# pcb1_12V.net
KiCad netlist of a schematic drawn in EAGLE
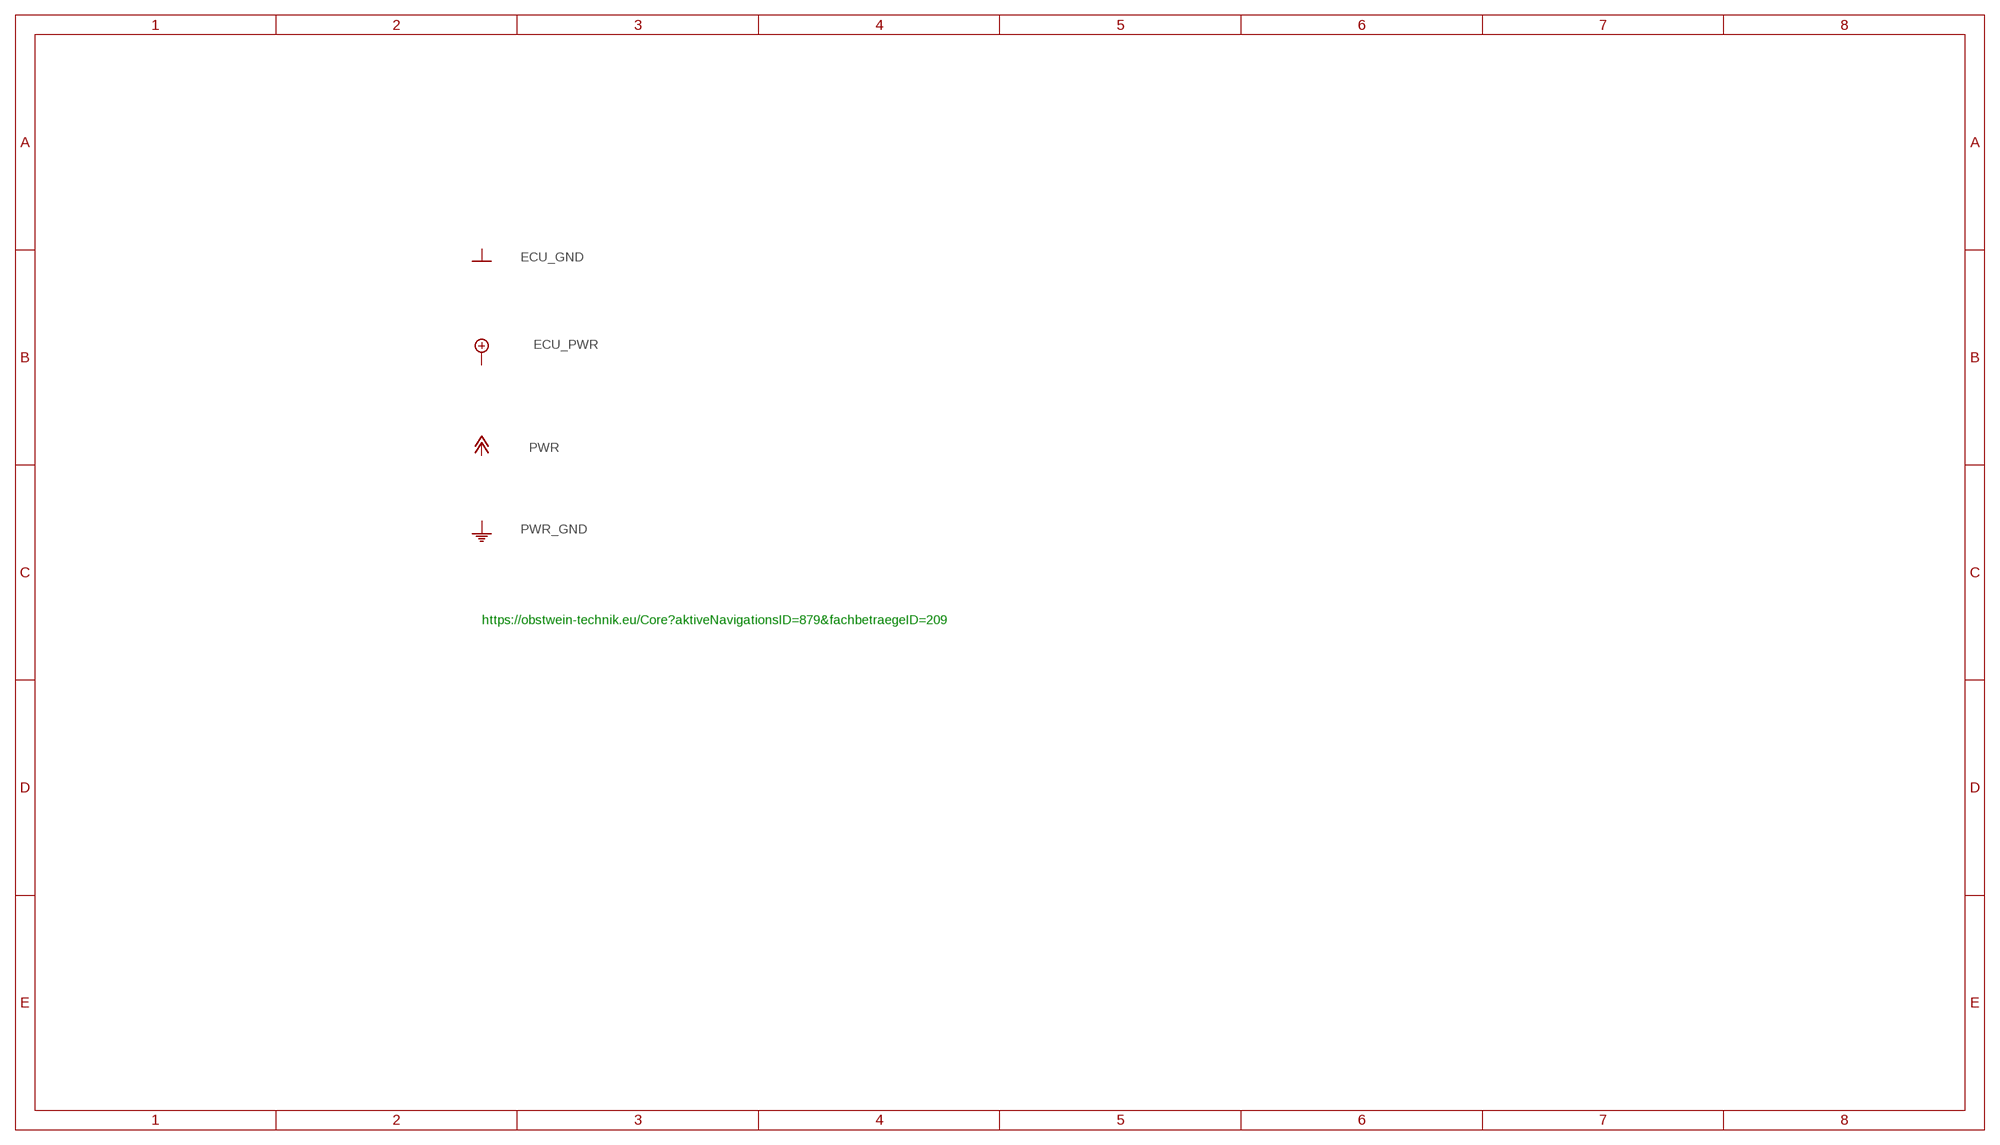
[diagram p0: schematic, sheet 1]
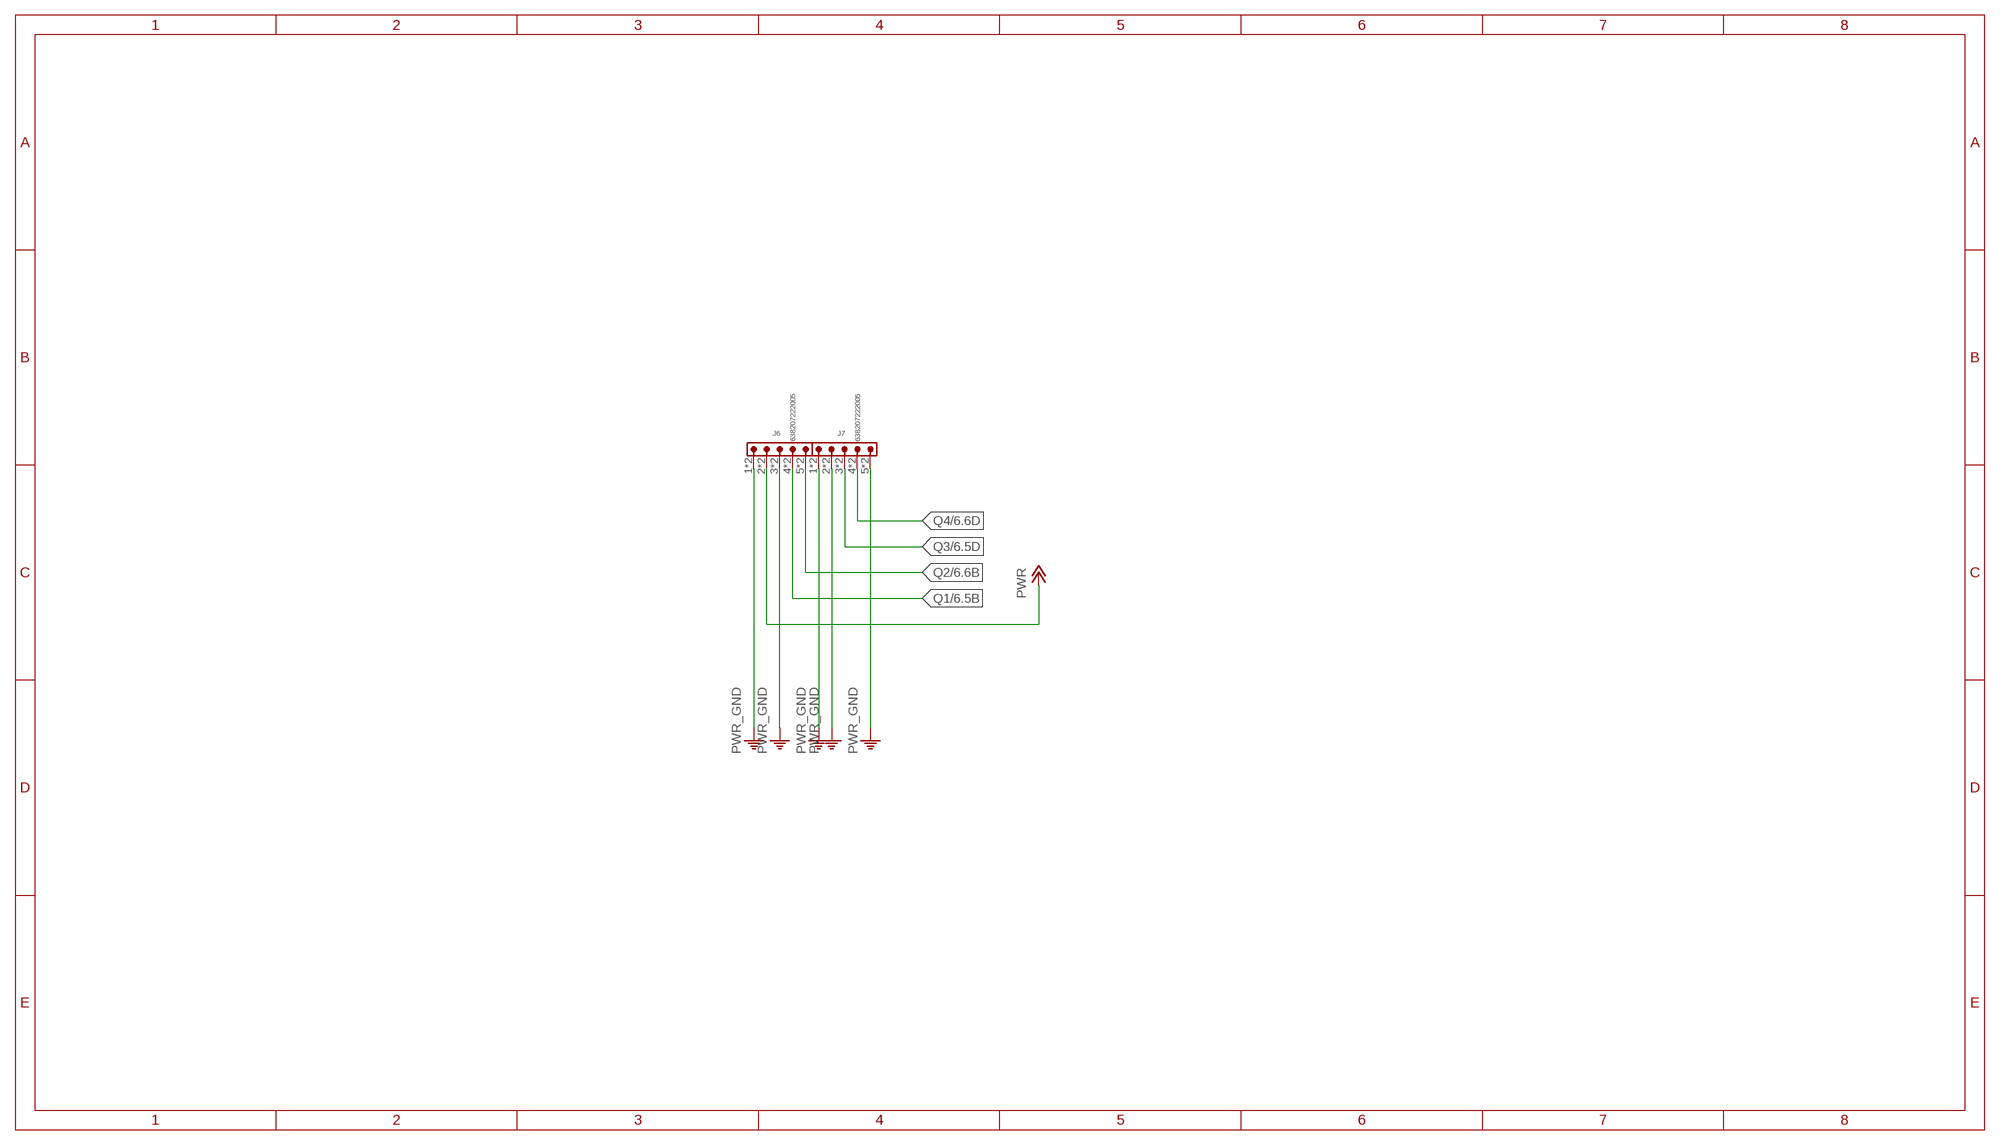
[diagram p1: schematic, sheet 2]
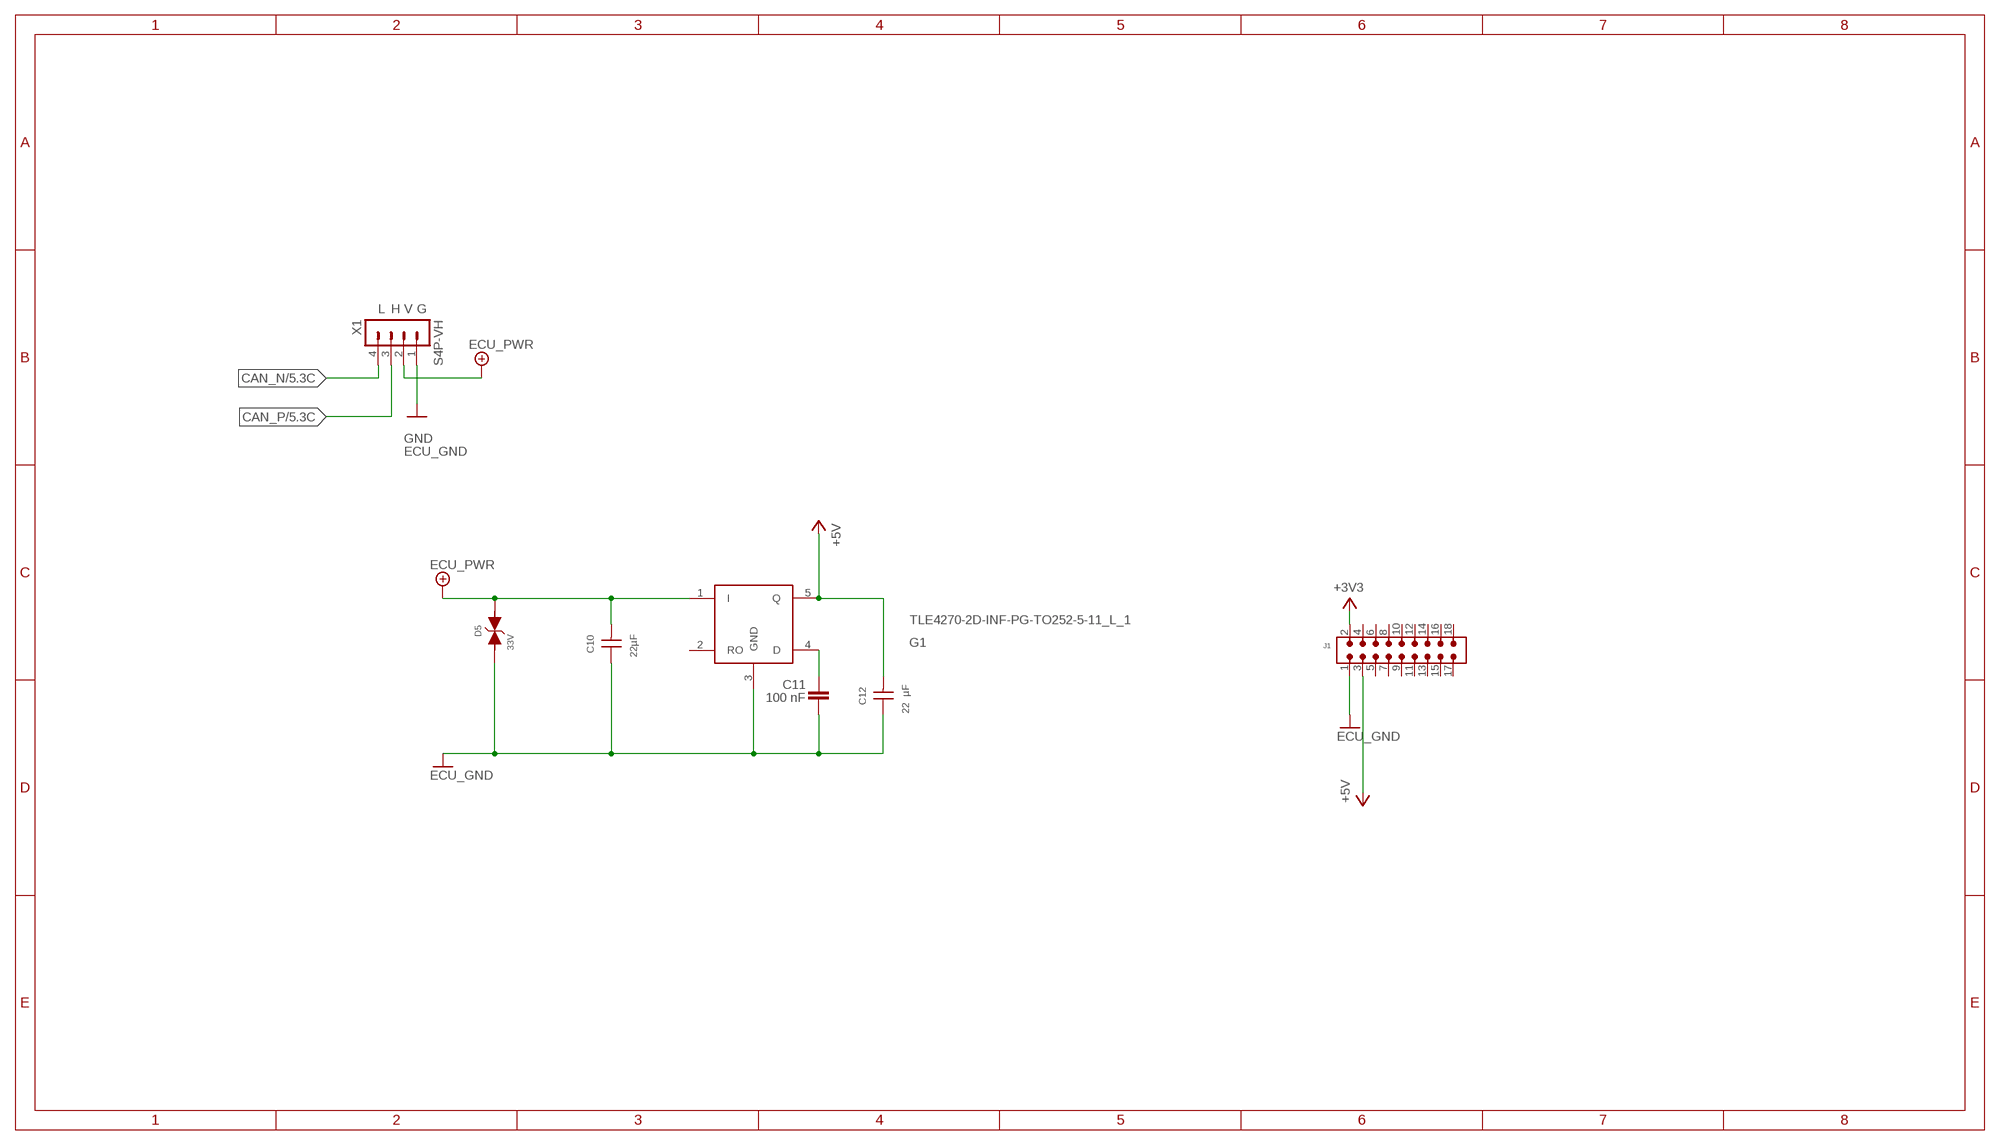
[diagram p2: schematic, sheet 3]
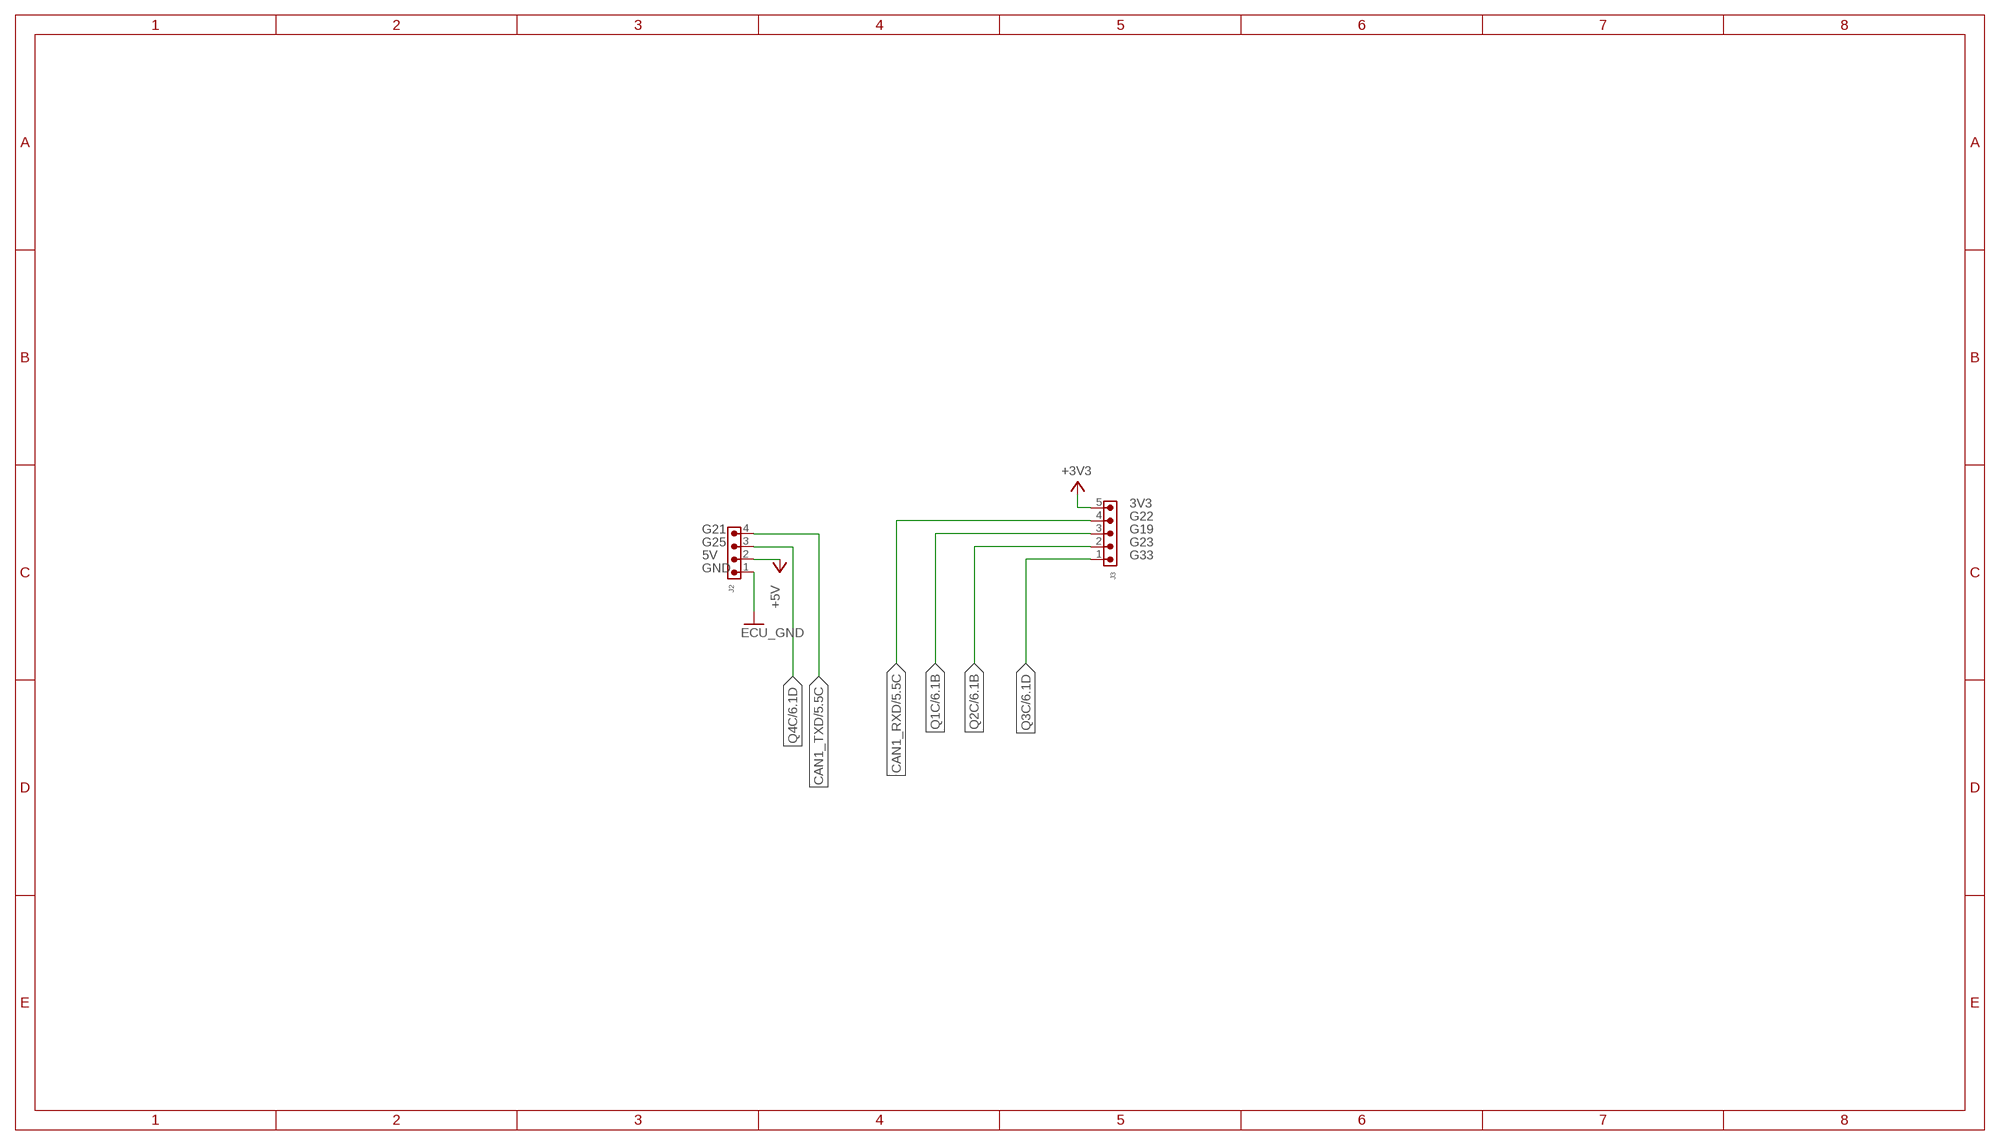
[diagram p3: schematic, sheet 4]
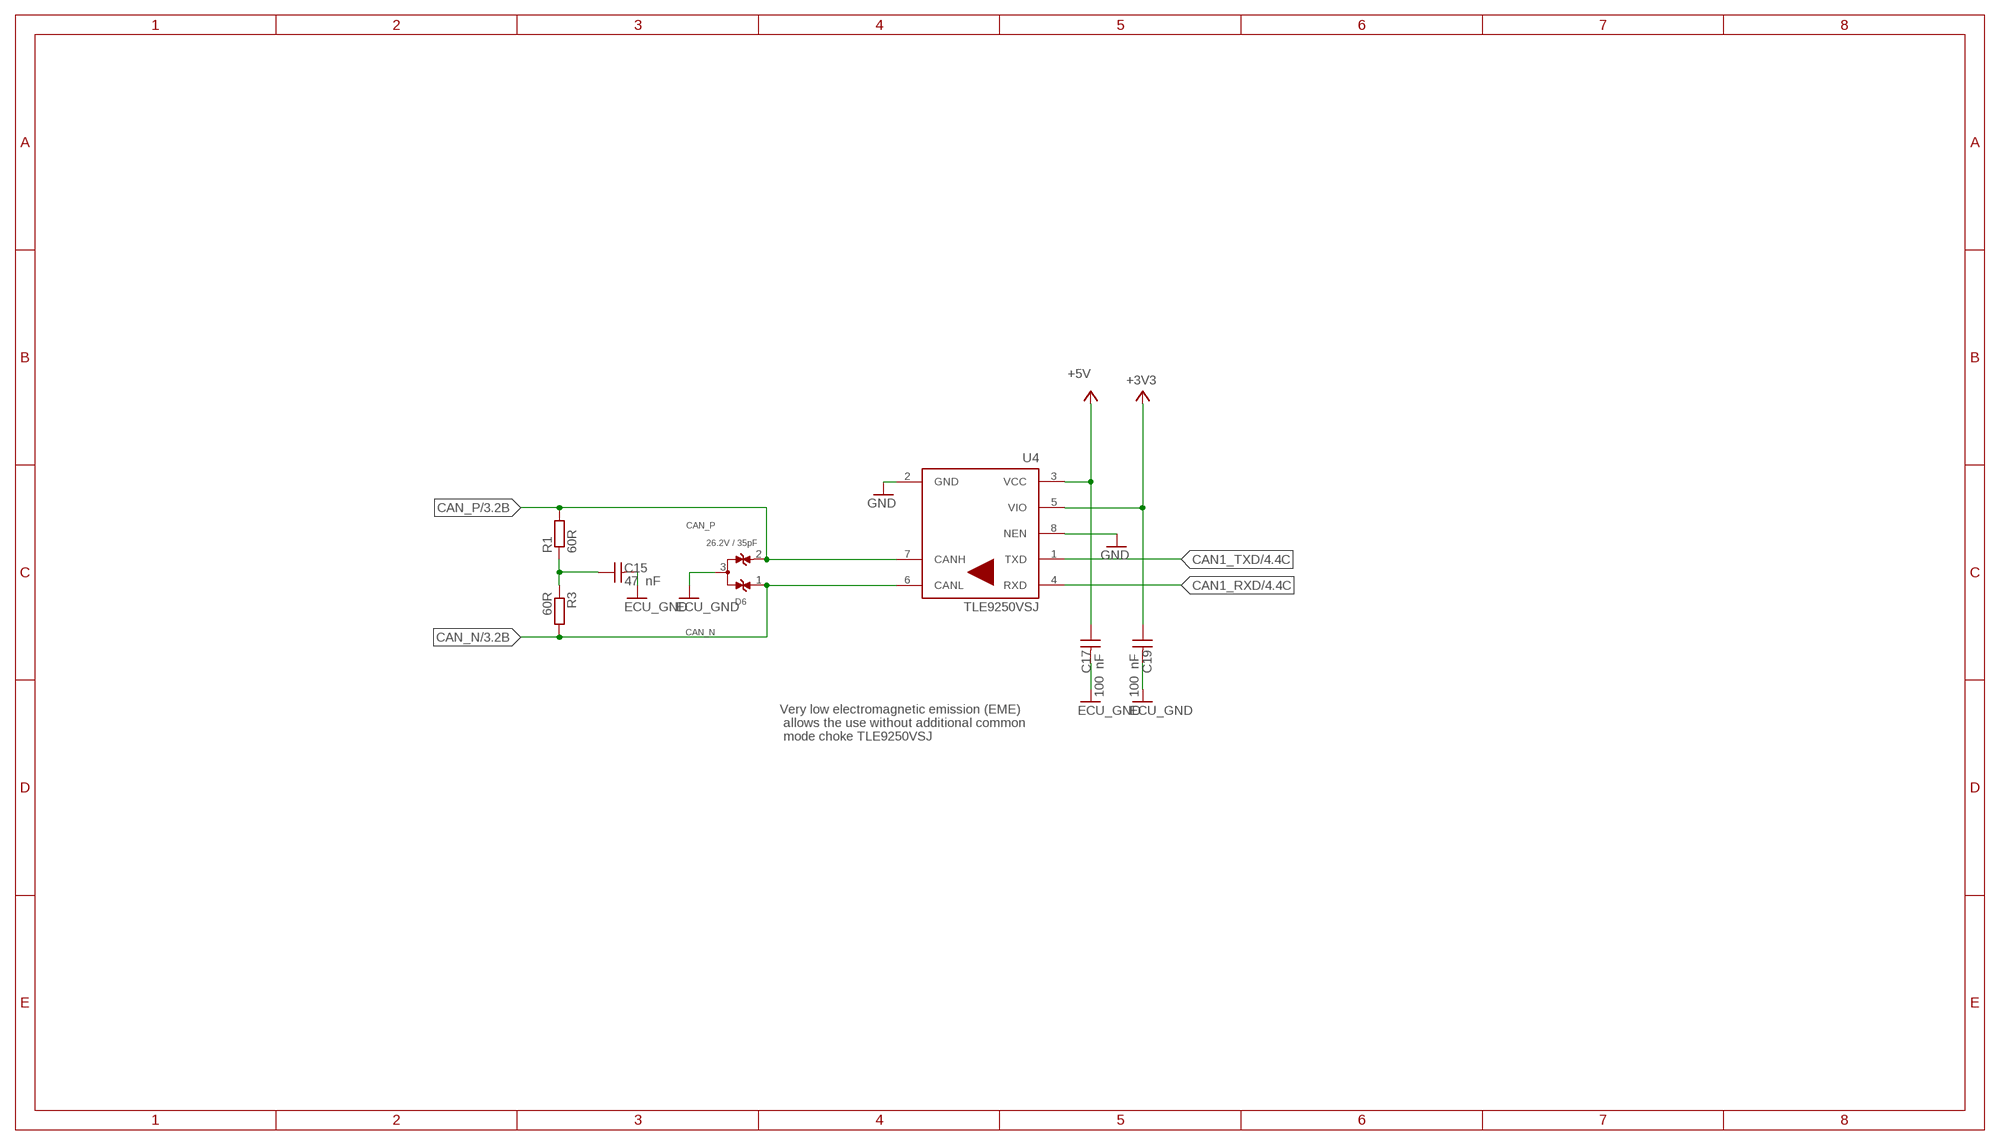
[diagram p4: schematic, sheet 5]
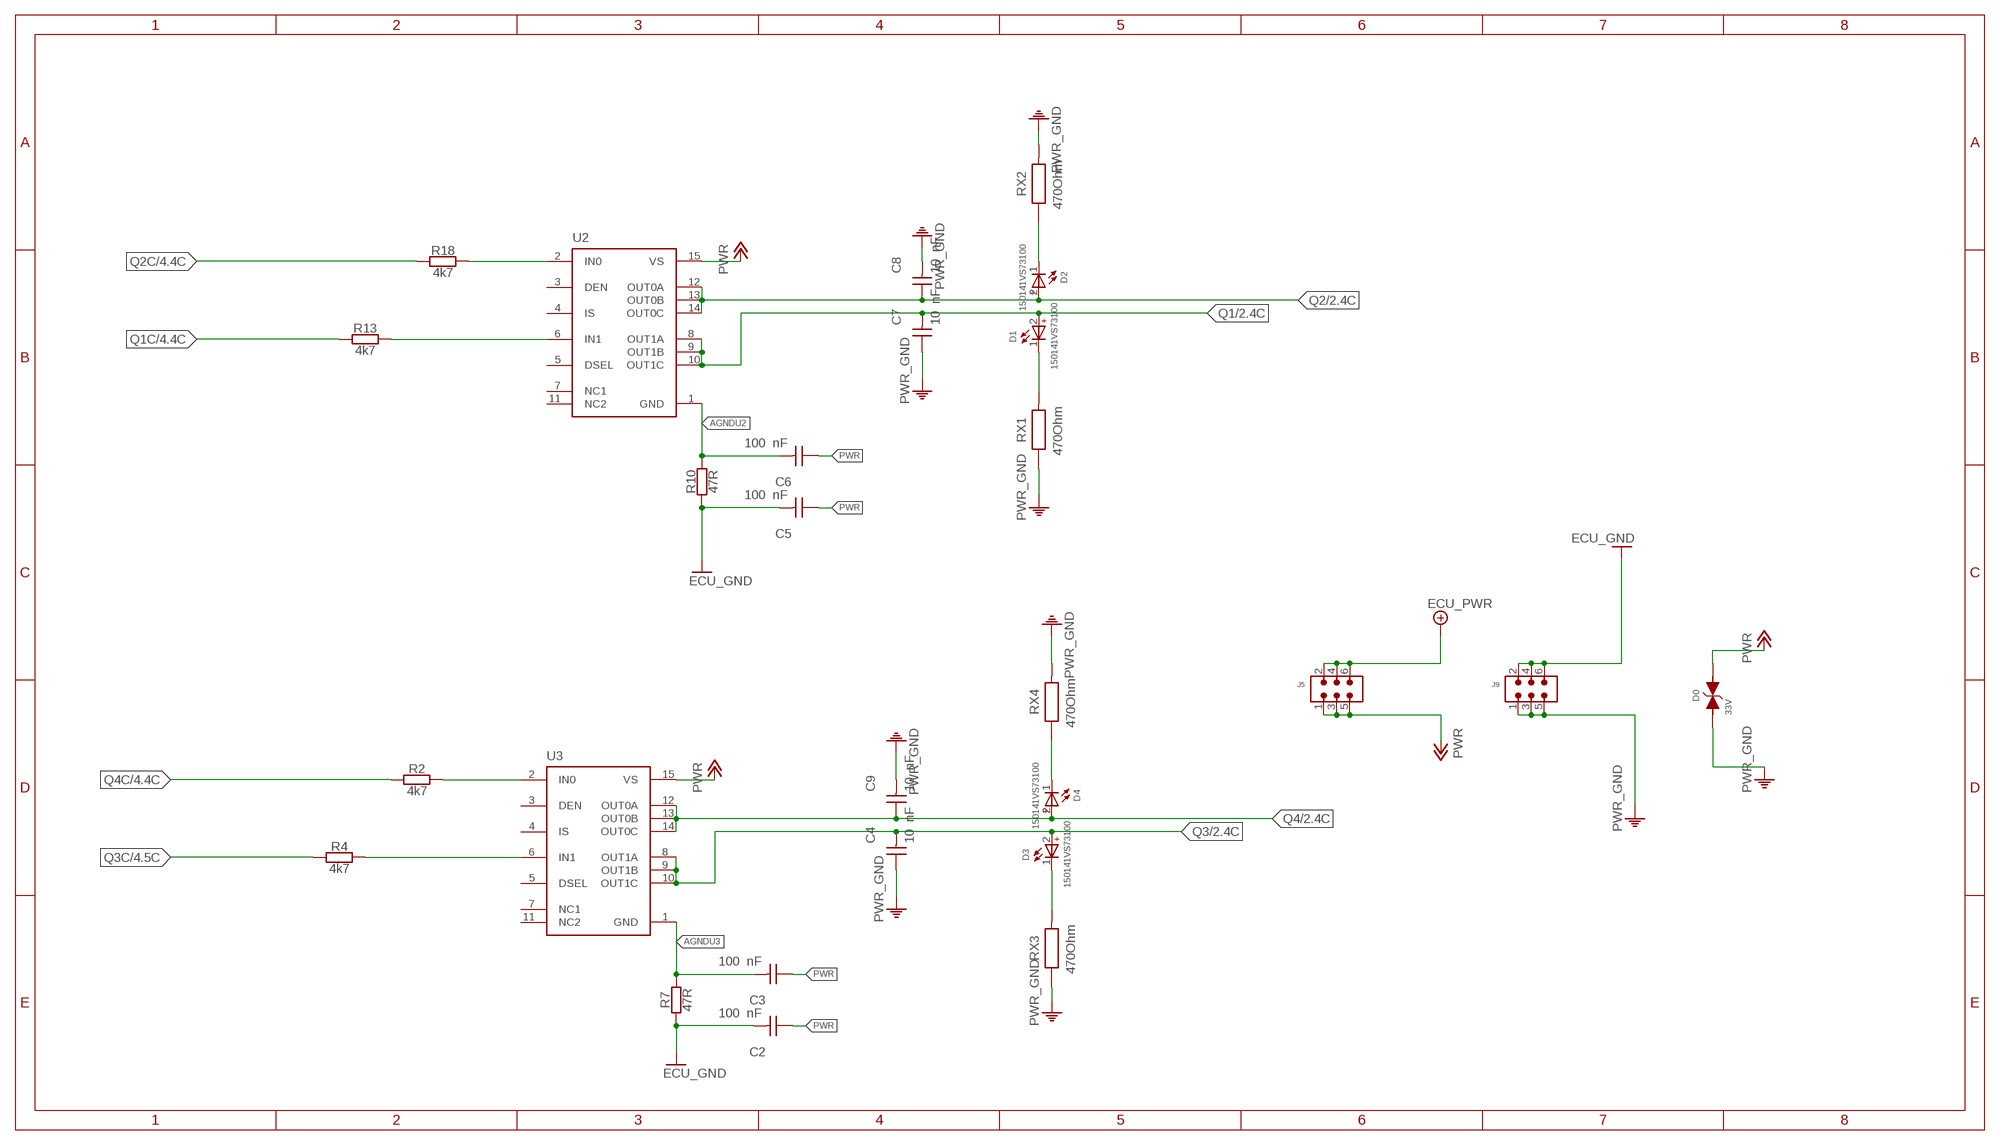
[diagram p5: schematic, sheet 6]

(export (version "E")
  (design (tool "Eeschema 10.0.6"))
  (components
    (comp (ref "C10")
      (value "22µF")
      (footprint "eagle-import:WCAP-CSGP_1210_H2.5")
      (libsource (lib "eagle-import") (part "WCAP-CSGP_1210_H2.5_25V(DC)_885012109014"))
    )
    (comp (ref "C11")
      (value "100 nF")
      (footprint "eagle-import:WCAP-CSGP_0402")
      (libsource (lib "eagle-import") (part "WCAP-CSGP_0402_16V(DC)_885012205037"))
    )
    (comp (ref "C12")
      (value "22 µF")
      (footprint "eagle-import:WCAP-CSGP_0805_H1.25_R")
      (libsource (lib "eagle-import") (part "WCAP-CSGP_0805_H1.25_10V(DC)_885012107011"))
    )
    (comp (ref "D5")
      (value "33V")
      (footprint "eagle-import:WE-TVSP_DO-214AB_BIDIRECTIONAL")
      (libsource (lib "eagle-import") (part "WE-TVSP_DO-214AB_3000W_BI_824551331"))
    )
    (comp (ref "G1")
      (value "TLE4270-2D-INF-PG-TO252-5-11_L_1")
      (footprint "eagle-import:INF-PG-TO252-5-11_L_1PRIMARY")
      (libsource (lib "eagle-import") (part "TLE4270-2D-INF-PG-TO252-5-11_L_1"))
    )
    (comp (ref "J1")
      (value "6130XX21121_61301821121")
      (footprint "eagle-import:61301821121")
      (libsource (lib "eagle-import") (part "6130XX21121_61301821121"))
    )
    (comp (ref "X1")
      (value "S4P-VH")
      (footprint "eagle-import:S4P-VH")
      (libsource (lib "eagle-import") (part "S4P-VH"))
    )
    (comp (ref "C15")
      (value "47 nF")
      (footprint "eagle-import:WCAP-CSGP_0805_H0.8_R")
      (libsource (lib "eagle-import") (part "WCAP-CSGP_0805_H0.8_50V(DC)_R_885012207096"))
    )
    (comp (ref "C17")
      (value "100 nF")
      (footprint "eagle-import:WCAP-CSGP_0805_H0.8_R")
      (libsource (lib "eagle-import") (part "WCAP-CSGP_0805_H0.8_50V(DC)_R_885012207098"))
    )
    (comp (ref "C19")
      (value "100 nF")
      (footprint "eagle-import:WCAP-CSGP_0805_H0.8_R")
      (libsource (lib "eagle-import") (part "WCAP-CSGP_0805_H0.8_50V(DC)_R_885012207098"))
    )
    (comp (ref "D6")
      (value "26.2V / 35pF")
      (footprint "eagle-import:WE-TVS_SOT23-3L")
      (libsource (lib "eagle-import") (part "WE-TVS_SOT23-3L_824098024"))
    )
    (comp (ref "R1")
      (value "60R")
      (footprint "eagle-import:R0805")
      (libsource (lib "eagle-import") (part "R-EU_R0805"))
    )
    (comp (ref "R3")
      (value "60R")
      (footprint "eagle-import:R0805")
      (libsource (lib "eagle-import") (part "R-EU_R0805"))
    )
    (comp (ref "U4")
      (value "TLE9250VSJ")
      (footprint "eagle-import:SOIC127P602X173-8N-V")
      (libsource (lib "eagle-import") (part "TLE9250VSJ"))
    )
    (comp (ref "J2")
      (value "6130XX11121_61300411121")
      (footprint "eagle-import:61300411121")
      (libsource (lib "eagle-import") (part "6130XX11121_61300411121"))
    )
    (comp (ref "J3")
      (value "6130XX11121_61300511121")
      (footprint "eagle-import:61300511121")
      (libsource (lib "eagle-import") (part "6130XX11121_61300511121"))
    )
    (comp (ref "C2")
      (value "100 nF")
      (footprint "eagle-import:WCAP-CSGP_0805_H0.8_R")
      (libsource (lib "eagle-import") (part "WCAP-CSGP_0805_H0.8_50V(DC)_R_885012207098"))
    )
    (comp (ref "C3")
      (value "100 nF")
      (footprint "eagle-import:WCAP-CSGP_0805_H0.8_R")
      (libsource (lib "eagle-import") (part "WCAP-CSGP_0805_H0.8_50V(DC)_R_885012207098"))
    )
    (comp (ref "C4")
      (value "10 nF")
      (footprint "eagle-import:WCAP-CSGP_0805_H0.8_R")
      (libsource (lib "eagle-import") (part "WCAP-CSGP_0805_H0.8_50V(DC)_R_885012207092"))
    )
    (comp (ref "C5")
      (value "100 nF")
      (footprint "eagle-import:WCAP-CSGP_0805_H0.8_R")
      (libsource (lib "eagle-import") (part "WCAP-CSGP_0805_H0.8_50V(DC)_R_885012207098"))
    )
    (comp (ref "C6")
      (value "100 nF")
      (footprint "eagle-import:WCAP-CSGP_0805_H0.8_R")
      (libsource (lib "eagle-import") (part "WCAP-CSGP_0805_H0.8_50V(DC)_R_885012207098"))
    )
    (comp (ref "C7")
      (value "10 nF")
      (footprint "eagle-import:WCAP-CSGP_0805_H0.8_R")
      (libsource (lib "eagle-import") (part "WCAP-CSGP_0805_H0.8_50V(DC)_R_885012207092"))
    )
    (comp (ref "C8")
      (value "10 nF")
      (footprint "eagle-import:WCAP-CSGP_0805_H0.8_R")
      (libsource (lib "eagle-import") (part "WCAP-CSGP_0805_H0.8_50V(DC)_R_885012207092"))
    )
    (comp (ref "C9")
      (value "10 nF")
      (footprint "eagle-import:WCAP-CSGP_0805_H0.8_R")
      (libsource (lib "eagle-import") (part "WCAP-CSGP_0805_H0.8_50V(DC)_R_885012207092"))
    )
    (comp (ref "D0")
      (value "33V")
      (footprint "eagle-import:WE-TVSP_DO-214AB_BIDIRECTIONAL")
      (libsource (lib "eagle-import") (part "WE-TVSP_DO-214AB_3000W_BI_824551331"))
    )
    (comp (ref "D1")
      (value "150141VS73100")
      (footprint "eagle-import:WL-SMTW_3528")
      (libsource (lib "eagle-import") (part "WL-SMTW_3528_150141VS73100"))
    )
    (comp (ref "D2")
      (value "150141VS73100")
      (footprint "eagle-import:WL-SMTW_3528")
      (libsource (lib "eagle-import") (part "WL-SMTW_3528_150141VS73100"))
    )
    (comp (ref "D3")
      (value "150141VS73100")
      (footprint "eagle-import:WL-SMTW_3528")
      (libsource (lib "eagle-import") (part "WL-SMTW_3528_150141VS73100"))
    )
    (comp (ref "D4")
      (value "150141VS73100")
      (footprint "eagle-import:WL-SMTW_3528")
      (libsource (lib "eagle-import") (part "WL-SMTW_3528_150141VS73100"))
    )
    (comp (ref "J5")
      (value "6130XX21121_61300621121")
      (footprint "eagle-import:61300621121")
      (libsource (lib "eagle-import") (part "6130XX21121_61300621121"))
    )
    (comp (ref "J9")
      (value "6130XX21121_61300621121")
      (footprint "eagle-import:61300621121")
      (libsource (lib "eagle-import") (part "6130XX21121_61300621121"))
    )
    (comp (ref "R2")
      (value "4k7")
      (footprint "eagle-import:R0805")
      (libsource (lib "eagle-import") (part "R-EU_R0805"))
    )
    (comp (ref "R4")
      (value "4k7")
      (footprint "eagle-import:R0805")
      (libsource (lib "eagle-import") (part "R-EU_R0805"))
    )
    (comp (ref "R7")
      (value "47R")
      (footprint "eagle-import:R0805")
      (libsource (lib "eagle-import") (part "R-EU_R0805"))
    )
    (comp (ref "R10")
      (value "47R")
      (footprint "eagle-import:R0805")
      (libsource (lib "eagle-import") (part "R-EU_R0805"))
    )
    (comp (ref "R13")
      (value "4k7")
      (footprint "eagle-import:R0805")
      (libsource (lib "eagle-import") (part "R-EU_R0805"))
    )
    (comp (ref "R18")
      (value "4k7")
      (footprint "eagle-import:R0805")
      (libsource (lib "eagle-import") (part "R-EU_R0805"))
    )
    (comp (ref "RX1")
      (value "470Ohm")
      (footprint "eagle-import:WRIS-KWKB_0612")
      (libsource (lib "eagle-import") (part "WRIS-KWKB_0612_561020132023"))
    )
    (comp (ref "RX2")
      (value "470Ohm")
      (footprint "eagle-import:WRIS-KWKB_0612")
      (libsource (lib "eagle-import") (part "WRIS-KWKB_0612_561020132023"))
    )
    (comp (ref "RX3")
      (value "470Ohm")
      (footprint "eagle-import:WRIS-KWKB_0612")
      (libsource (lib "eagle-import") (part "WRIS-KWKB_0612_561020132023"))
    )
    (comp (ref "RX4")
      (value "470Ohm")
      (footprint "eagle-import:WRIS-KWKB_0612")
      (libsource (lib "eagle-import") (part "WRIS-KWKB_0612_561020132023"))
    )
    (comp (ref "U2")
      (value "BTS7030-2EPA")
      (footprint "eagle-import:SOP65P600X115-15N-V")
      (libsource (lib "eagle-import") (part "BTS7030-2EPA"))
    )
    (comp (ref "U3")
      (value "BTS7030-2EPA")
      (footprint "eagle-import:SOP65P600X115-15N-V")
      (libsource (lib "eagle-import") (part "BTS7030-2EPA"))
    )
    (comp (ref "J6")
      (value "638207222005")
      (footprint "eagle-import:638207222005")
      (libsource (lib "eagle-import") (part "638207222005"))
    )
    (comp (ref "J7")
      (value "638207222005")
      (footprint "eagle-import:638207222005")
      (libsource (lib "eagle-import") (part "638207222005"))
    )
  )
  (nets
    (net (code "1") (name "+3V3") (class "Default")
      (node (ref "C19") (pin "1") (pinfunction "1_1") (pintype "passive"))
      (node (ref "J1") (pin "2") (pinfunction "2_2") (pintype "passive"))
      (node (ref "J3") (pin "5") (pinfunction "5_5") (pintype "passive"))
      (node (ref "U4") (pin "5") (pinfunction "VIO_5") (pintype "input"))
    )
    (net (code "2") (name "+5V") (class "Default")
      (node (ref "C12") (pin "2") (pinfunction "2_2") (pintype "passive"))
      (node (ref "C17") (pin "1") (pinfunction "1_1") (pintype "passive"))
      (node (ref "G1") (pin "5") (pinfunction "Q_5") (pintype "power_in"))
      (node (ref "J1") (pin "3") (pinfunction "3_3") (pintype "passive"))
      (node (ref "J2") (pin "2") (pinfunction "2_2") (pintype "passive"))
      (node (ref "U4") (pin "3") (pinfunction "VCC_3") (pintype "input"))
    )
    (net (code "3") (name "AGNDU2") (class "Default")
      (node (ref "C6") (pin "2") (pinfunction "2_2") (pintype "passive"))
      (node (ref "R10") (pin "2") (pinfunction "2_2") (pintype "passive"))
      (node (ref "U2") (pin "1") (pinfunction "GND_1") (pintype "power_in"))
    )
    (net (code "4") (name "AGNDU3") (class "Default")
      (node (ref "C3") (pin "2") (pinfunction "2_2") (pintype "passive"))
      (node (ref "R7") (pin "2") (pinfunction "2_2") (pintype "passive"))
      (node (ref "U3") (pin "1") (pinfunction "GND_1") (pintype "power_in"))
    )
    (net (code "5") (name "CAN1_RXD") (class "Default")
      (node (ref "J3") (pin "4") (pinfunction "4_4") (pintype "passive"))
      (node (ref "U4") (pin "4") (pinfunction "RXD_4") (pintype "output"))
    )
    (net (code "6") (name "CAN1_TXD") (class "Default")
      (node (ref "J2") (pin "4") (pinfunction "4_4") (pintype "passive"))
      (node (ref "U4") (pin "1") (pinfunction "TXD_1") (pintype "input"))
    )
    (net (code "7") (name "CAN_N") (class "Default")
      (node (ref "D6") (pin "1") (pinfunction "1_1") (pintype "passive"))
      (node (ref "R3") (pin "2") (pinfunction "2_2") (pintype "passive"))
      (node (ref "U4") (pin "6") (pinfunction "CANL_6") (pintype "bidirectional"))
      (node (ref "X1") (pin "4") (pinfunction "4_4") (pintype "passive"))
    )
    (net (code "8") (name "CAN_P") (class "Default")
      (node (ref "D6") (pin "2") (pinfunction "2_2") (pintype "passive"))
      (node (ref "R1") (pin "2") (pinfunction "2_2") (pintype "passive"))
      (node (ref "U4") (pin "7") (pinfunction "CANH_7") (pintype "bidirectional"))
      (node (ref "X1") (pin "3") (pinfunction "3_3") (pintype "passive"))
    )
    (net (code "9") (name "ECU_GND") (class "Default")
      (node (ref "C10") (pin "1") (pinfunction "1_1") (pintype "passive"))
      (node (ref "C11") (pin "2") (pinfunction "2_2") (pintype "passive"))
      (node (ref "C12") (pin "1") (pinfunction "1_1") (pintype "passive"))
      (node (ref "C15") (pin "2") (pinfunction "2_2") (pintype "passive"))
      (node (ref "C17") (pin "2") (pinfunction "2_2") (pintype "passive"))
      (node (ref "C19") (pin "2") (pinfunction "2_2") (pintype "passive"))
      (node (ref "C2") (pin "2") (pinfunction "2_2") (pintype "passive"))
      (node (ref "C5") (pin "2") (pinfunction "2_2") (pintype "passive"))
      (node (ref "D5") (pin "1") (pinfunction "1_1") (pintype "passive"))
      (node (ref "D6") (pin "3") (pinfunction "3_3") (pintype "passive"))
      (node (ref "G1") (pin "3") (pinfunction "GND_3") (pintype "power_in"))
      (node (ref "J1") (pin "1") (pinfunction "1_1") (pintype "passive"))
      (node (ref "J2") (pin "1") (pinfunction "1_1") (pintype "passive"))
      (node (ref "J9") (pin "2") (pinfunction "2_2") (pintype "passive"))
      (node (ref "J9") (pin "4") (pinfunction "4_4") (pintype "passive"))
      (node (ref "J9") (pin "6") (pinfunction "6_6") (pintype "passive"))
      (node (ref "R10") (pin "1") (pinfunction "1_1") (pintype "passive"))
      (node (ref "R7") (pin "1") (pinfunction "1_1") (pintype "passive"))
      (node (ref "U4") (pin "2") (pinfunction "GND_2") (pintype "power_in"))
      (node (ref "U4") (pin "8") (pinfunction "NEN_8") (pintype "input"))
      (node (ref "X1") (pin "1") (pinfunction "1_1") (pintype "passive"))
    )
    (net (code "10") (name "ECU_PWR") (class "Default")
      (node (ref "C10") (pin "2") (pinfunction "2_2") (pintype "passive"))
      (node (ref "D5") (pin "2") (pinfunction "2_2") (pintype "passive"))
      (node (ref "G1") (pin "1") (pinfunction "I_1") (pintype "power_in"))
      (node (ref "J5") (pin "2") (pinfunction "2_2") (pintype "passive"))
      (node (ref "J5") (pin "4") (pinfunction "4_4") (pintype "passive"))
      (node (ref "J5") (pin "6") (pinfunction "6_6") (pintype "passive"))
      (node (ref "X1") (pin "2") (pinfunction "2_2") (pintype "passive"))
    )
    (net (code "11") (name "Net-(C15-Pad1)") (class "Default")
      (node (ref "C15") (pin "1") (pinfunction "1_1") (pintype "passive"))
      (node (ref "R1") (pin "1") (pinfunction "1_1") (pintype "passive"))
      (node (ref "R3") (pin "1") (pinfunction "1_1") (pintype "passive"))
    )
    (net (code "12") (name "Net-(D1--)") (class "Default")
      (node (ref "D1") (pin "1") (pinfunction "-_1") (pintype "passive"))
      (node (ref "RX1") (pin "2") (pinfunction "2_2") (pintype "passive"))
    )
    (net (code "13") (name "Net-(D2--)") (class "Default")
      (node (ref "D2") (pin "1") (pinfunction "-_1") (pintype "passive"))
      (node (ref "RX2") (pin "1") (pinfunction "1_1") (pintype "passive"))
    )
    (net (code "14") (name "Net-(D3--)") (class "Default")
      (node (ref "D3") (pin "1") (pinfunction "-_1") (pintype "passive"))
      (node (ref "RX3") (pin "2") (pinfunction "2_2") (pintype "passive"))
    )
    (net (code "15") (name "Net-(D4--)") (class "Default")
      (node (ref "D4") (pin "1") (pinfunction "-_1") (pintype "passive"))
      (node (ref "RX4") (pin "1") (pinfunction "1_1") (pintype "passive"))
    )
    (net (code "16") (name "Net-(G1-D)") (class "Default")
      (node (ref "C11") (pin "1") (pinfunction "1_1") (pintype "passive"))
      (node (ref "G1") (pin "4") (pinfunction "D_4") (pintype "bidirectional"))
    )
    (net (code "17") (name "Net-(U2-IN0)") (class "Default")
      (node (ref "R18") (pin "2") (pinfunction "2_2") (pintype "passive"))
      (node (ref "U2") (pin "2") (pinfunction "IN0_2") (pintype "input"))
    )
    (net (code "18") (name "Net-(U2-IN1)") (class "Default")
      (node (ref "R13") (pin "2") (pinfunction "2_2") (pintype "passive"))
      (node (ref "U2") (pin "6") (pinfunction "IN1_6") (pintype "input"))
    )
    (net (code "19") (name "Net-(U3-IN0)") (class "Default")
      (node (ref "R2") (pin "2") (pinfunction "2_2") (pintype "passive"))
      (node (ref "U3") (pin "2") (pinfunction "IN0_2") (pintype "input"))
    )
    (net (code "20") (name "Net-(U3-IN1)") (class "Default")
      (node (ref "R4") (pin "2") (pinfunction "2_2") (pintype "passive"))
      (node (ref "U3") (pin "6") (pinfunction "IN1_6") (pintype "input"))
    )
    (net (code "21") (name "PWR") (class "Default")
      (node (ref "C2") (pin "1") (pinfunction "1_1") (pintype "passive"))
      (node (ref "C3") (pin "1") (pinfunction "1_1") (pintype "passive"))
      (node (ref "C5") (pin "1") (pinfunction "1_1") (pintype "passive"))
      (node (ref "C6") (pin "1") (pinfunction "1_1") (pintype "passive"))
      (node (ref "D0") (pin "2") (pinfunction "2_2") (pintype "passive"))
      (node (ref "J5") (pin "1") (pinfunction "1_1") (pintype "passive"))
      (node (ref "J5") (pin "3") (pinfunction "3_3") (pintype "passive"))
      (node (ref "J5") (pin "5") (pinfunction "5_5") (pintype "passive"))
      (node (ref "J6") (pin "2") (pinfunction "2_2") (pintype "passive"))
      (node (ref "J6") (pin "A2") (pinfunction "2_A2") (pintype "passive"))
      (node (ref "U2") (pin "15") (pinfunction "VS_15") (pintype "power_in"))
      (node (ref "U3") (pin "15") (pinfunction "VS_15") (pintype "power_in"))
    )
    (net (code "22") (name "PWR_GND") (class "Default")
      (node (ref "C4") (pin "1") (pinfunction "1_1") (pintype "passive"))
      (node (ref "C7") (pin "1") (pinfunction "1_1") (pintype "passive"))
      (node (ref "C8") (pin "2") (pinfunction "2_2") (pintype "passive"))
      (node (ref "C9") (pin "2") (pinfunction "2_2") (pintype "passive"))
      (node (ref "D0") (pin "1") (pinfunction "1_1") (pintype "passive"))
      (node (ref "J6") (pin "1") (pinfunction "1_1") (pintype "passive"))
      (node (ref "J6") (pin "3") (pinfunction "3_3") (pintype "passive"))
      (node (ref "J6") (pin "A1") (pinfunction "1_A1") (pintype "passive"))
      (node (ref "J6") (pin "A3") (pinfunction "3_A3") (pintype "passive"))
      (node (ref "J7") (pin "1") (pinfunction "1_1") (pintype "passive"))
      (node (ref "J7") (pin "2") (pinfunction "2_2") (pintype "passive"))
      (node (ref "J7") (pin "5") (pinfunction "5_5") (pintype "passive"))
      (node (ref "J7") (pin "A1") (pinfunction "1_A1") (pintype "passive"))
      (node (ref "J7") (pin "A2") (pinfunction "2_A2") (pintype "passive"))
      (node (ref "J7") (pin "A5") (pinfunction "5_A5") (pintype "passive"))
      (node (ref "J9") (pin "1") (pinfunction "1_1") (pintype "passive"))
      (node (ref "J9") (pin "3") (pinfunction "3_3") (pintype "passive"))
      (node (ref "J9") (pin "5") (pinfunction "5_5") (pintype "passive"))
      (node (ref "RX1") (pin "1") (pinfunction "1_1") (pintype "passive"))
      (node (ref "RX2") (pin "2") (pinfunction "2_2") (pintype "passive"))
      (node (ref "RX3") (pin "1") (pinfunction "1_1") (pintype "passive"))
      (node (ref "RX4") (pin "2") (pinfunction "2_2") (pintype "passive"))
    )
    (net (code "23") (name "Q1") (class "Default")
      (node (ref "C7") (pin "2") (pinfunction "2_2") (pintype "passive"))
      (node (ref "D1") (pin "2") (pinfunction "+_2") (pintype "passive"))
      (node (ref "J6") (pin "4") (pinfunction "4_4") (pintype "passive"))
      (node (ref "J6") (pin "A4") (pinfunction "4_A4") (pintype "passive"))
      (node (ref "U2") (pin "10") (pinfunction "OUT1C_10") (pintype "output"))
      (node (ref "U2") (pin "8") (pinfunction "OUT1A_8") (pintype "output"))
      (node (ref "U2") (pin "9") (pinfunction "OUT1B_9") (pintype "output"))
    )
    (net (code "24") (name "Q1C") (class "Default")
      (node (ref "J3") (pin "3") (pinfunction "3_3") (pintype "passive"))
      (node (ref "R13") (pin "1") (pinfunction "1_1") (pintype "passive"))
    )
    (net (code "25") (name "Q2") (class "Default")
      (node (ref "C8") (pin "1") (pinfunction "1_1") (pintype "passive"))
      (node (ref "D2") (pin "2") (pinfunction "+_2") (pintype "passive"))
      (node (ref "J6") (pin "5") (pinfunction "5_5") (pintype "passive"))
      (node (ref "J6") (pin "A5") (pinfunction "5_A5") (pintype "passive"))
      (node (ref "U2") (pin "12") (pinfunction "OUT0A_12") (pintype "output"))
      (node (ref "U2") (pin "13") (pinfunction "OUT0B_13") (pintype "output"))
      (node (ref "U2") (pin "14") (pinfunction "OUT0C_14") (pintype "output"))
    )
    (net (code "26") (name "Q2C") (class "Default")
      (node (ref "J3") (pin "2") (pinfunction "2_2") (pintype "passive"))
      (node (ref "R18") (pin "1") (pinfunction "1_1") (pintype "passive"))
    )
    (net (code "27") (name "Q3") (class "Default")
      (node (ref "C4") (pin "2") (pinfunction "2_2") (pintype "passive"))
      (node (ref "D3") (pin "2") (pinfunction "+_2") (pintype "passive"))
      (node (ref "J7") (pin "3") (pinfunction "3_3") (pintype "passive"))
      (node (ref "J7") (pin "A3") (pinfunction "3_A3") (pintype "passive"))
      (node (ref "U3") (pin "10") (pinfunction "OUT1C_10") (pintype "output"))
      (node (ref "U3") (pin "8") (pinfunction "OUT1A_8") (pintype "output"))
      (node (ref "U3") (pin "9") (pinfunction "OUT1B_9") (pintype "output"))
    )
    (net (code "28") (name "Q3C") (class "Default")
      (node (ref "J3") (pin "1") (pinfunction "1_1") (pintype "passive"))
      (node (ref "R4") (pin "1") (pinfunction "1_1") (pintype "passive"))
    )
    (net (code "29") (name "Q4") (class "Default")
      (node (ref "C9") (pin "1") (pinfunction "1_1") (pintype "passive"))
      (node (ref "D4") (pin "2") (pinfunction "+_2") (pintype "passive"))
      (node (ref "J7") (pin "4") (pinfunction "4_4") (pintype "passive"))
      (node (ref "J7") (pin "A4") (pinfunction "4_A4") (pintype "passive"))
      (node (ref "U3") (pin "12") (pinfunction "OUT0A_12") (pintype "output"))
      (node (ref "U3") (pin "13") (pinfunction "OUT0B_13") (pintype "output"))
      (node (ref "U3") (pin "14") (pinfunction "OUT0C_14") (pintype "output"))
    )
    (net (code "30") (name "Q4C") (class "Default")
      (node (ref "J2") (pin "3") (pinfunction "3_3") (pintype "passive"))
      (node (ref "R2") (pin "1") (pinfunction "1_1") (pintype "passive"))
    )
    (net (code "31") (name "unconnected-(G1-RO-Pad2)") (class "Default")
      (node (ref "G1") (pin "2") (pinfunction "RO_2") (pintype "output"))
    )
    (net (code "32") (name "unconnected-(J1-Pad4)") (class "Default")
      (node (ref "J1") (pin "4") (pinfunction "4_4") (pintype "passive"))
    )
    (net (code "33") (name "unconnected-(J1-Pad5)") (class "Default")
      (node (ref "J1") (pin "5") (pinfunction "5_5") (pintype "passive"))
    )
    (net (code "34") (name "unconnected-(J1-Pad6)") (class "Default")
      (node (ref "J1") (pin "6") (pinfunction "6_6") (pintype "passive"))
    )
    (net (code "35") (name "unconnected-(J1-Pad7)") (class "Default")
      (node (ref "J1") (pin "7") (pinfunction "7_7") (pintype "passive"))
    )
    (net (code "36") (name "unconnected-(J1-Pad8)") (class "Default")
      (node (ref "J1") (pin "8") (pinfunction "8_8") (pintype "passive"))
    )
    (net (code "37") (name "unconnected-(J1-Pad9)") (class "Default")
      (node (ref "J1") (pin "9") (pinfunction "9_9") (pintype "passive"))
    )
    (net (code "38") (name "unconnected-(J1-Pad10)") (class "Default")
      (node (ref "J1") (pin "10") (pinfunction "10_10") (pintype "passive"))
    )
    (net (code "39") (name "unconnected-(J1-Pad11)") (class "Default")
      (node (ref "J1") (pin "11") (pinfunction "11_11") (pintype "passive"))
    )
    (net (code "40") (name "unconnected-(J1-Pad12)") (class "Default")
      (node (ref "J1") (pin "12") (pinfunction "12_12") (pintype "passive"))
    )
    (net (code "41") (name "unconnected-(J1-Pad13)") (class "Default")
      (node (ref "J1") (pin "13") (pinfunction "13_13") (pintype "passive"))
    )
    (net (code "42") (name "unconnected-(J1-Pad14)") (class "Default")
      (node (ref "J1") (pin "14") (pinfunction "14_14") (pintype "passive"))
    )
    (net (code "43") (name "unconnected-(J1-Pad15)") (class "Default")
      (node (ref "J1") (pin "15") (pinfunction "15_15") (pintype "passive"))
    )
    (net (code "44") (name "unconnected-(J1-Pad16)") (class "Default")
      (node (ref "J1") (pin "16") (pinfunction "16_16") (pintype "passive"))
    )
    (net (code "45") (name "unconnected-(J1-Pad17)") (class "Default")
      (node (ref "J1") (pin "17") (pinfunction "17_17") (pintype "passive"))
    )
    (net (code "46") (name "unconnected-(J1-Pad18)") (class "Default")
      (node (ref "J1") (pin "18") (pinfunction "18_18") (pintype "passive"))
    )
    (net (code "47") (name "unconnected-(U2-DEN-Pad3)") (class "Default")
      (node (ref "U2") (pin "3") (pinfunction "DEN_3") (pintype "input"))
    )
    (net (code "48") (name "unconnected-(U2-DSEL-Pad5)") (class "Default")
      (node (ref "U2") (pin "5") (pinfunction "DSEL_5") (pintype "input"))
    )
    (net (code "49") (name "unconnected-(U2-IS-Pad4)") (class "Default")
      (node (ref "U2") (pin "4") (pinfunction "IS_4") (pintype "output"))
    )
    (net (code "50") (name "unconnected-(U2-NC1-Pad7)") (class "Default")
      (node (ref "U2") (pin "7") (pinfunction "NC1_7") (pintype "passive"))
    )
    (net (code "51") (name "unconnected-(U2-NC2-Pad11)") (class "Default")
      (node (ref "U2") (pin "11") (pinfunction "NC2_11") (pintype "passive"))
    )
    (net (code "52") (name "unconnected-(U3-DEN-Pad3)") (class "Default")
      (node (ref "U3") (pin "3") (pinfunction "DEN_3") (pintype "input"))
    )
    (net (code "53") (name "unconnected-(U3-DSEL-Pad5)") (class "Default")
      (node (ref "U3") (pin "5") (pinfunction "DSEL_5") (pintype "input"))
    )
    (net (code "54") (name "unconnected-(U3-IS-Pad4)") (class "Default")
      (node (ref "U3") (pin "4") (pinfunction "IS_4") (pintype "output"))
    )
    (net (code "55") (name "unconnected-(U3-NC1-Pad7)") (class "Default")
      (node (ref "U3") (pin "7") (pinfunction "NC1_7") (pintype "passive"))
    )
    (net (code "56") (name "unconnected-(U3-NC2-Pad11)") (class "Default")
      (node (ref "U3") (pin "11") (pinfunction "NC2_11") (pintype "passive"))
    )
  )
)
